# PIF_robot.net
KiCad netlist of a schematic drawn in Altium Designer
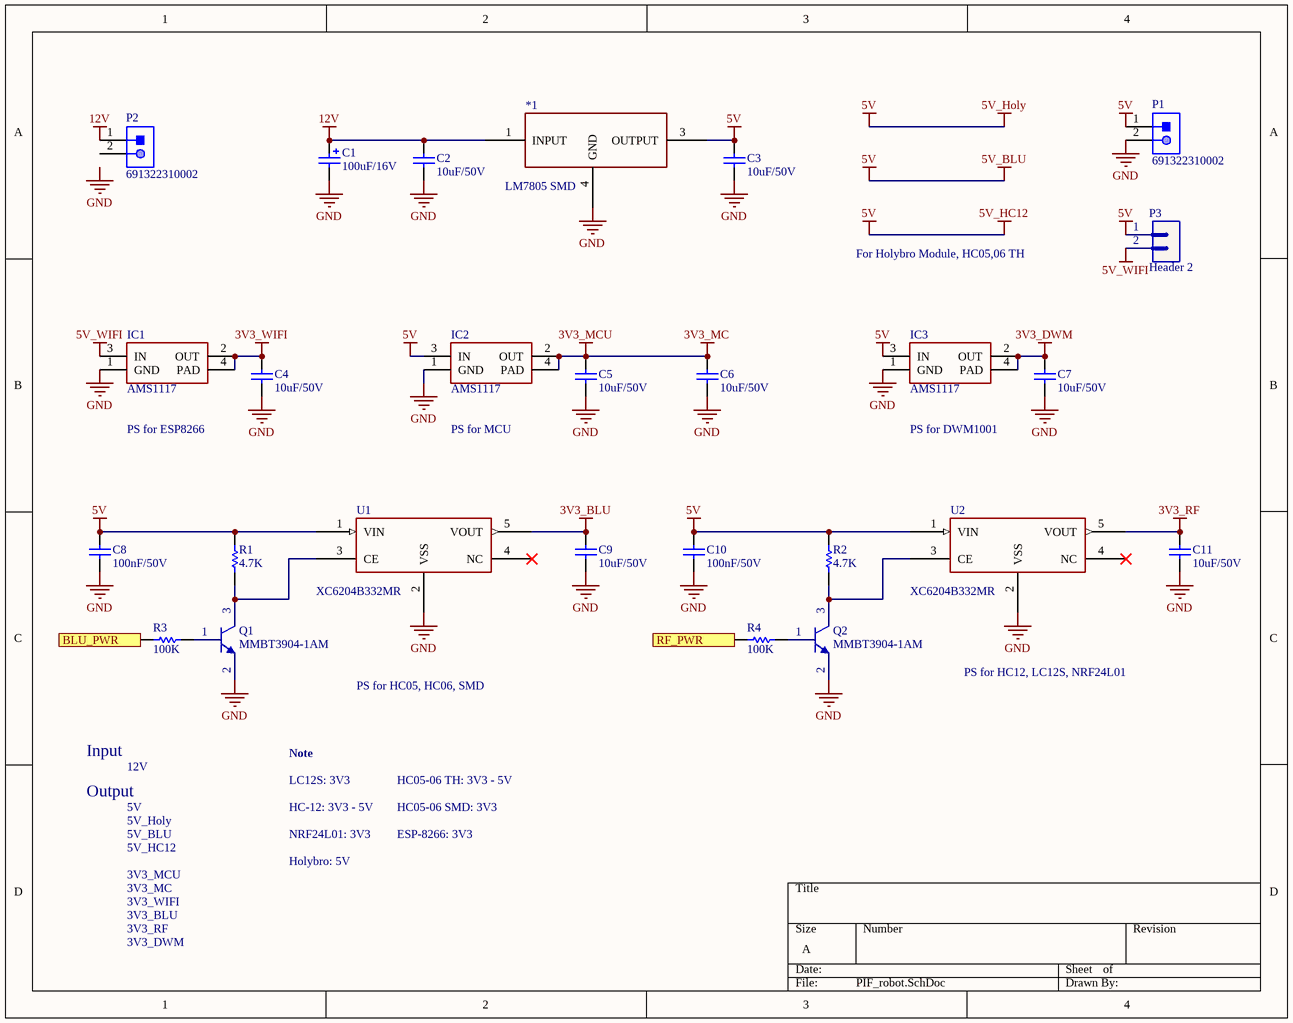
[diagram p0: PIF_robot.SchDoc]

(export (version "E")
  (design (tool "Eeschema 10.0.6"))
  (components
    (comp (ref "*1")
      (value "LM7805 SMD")
      (footprint "LM7805 SMD")
      (libsource (lib "PIF_robot") (part "LM7805 SMD"))
    )
    (comp (ref "C1")
      (value "100uF/16V")
      (footprint "CAP-SM-AL-SIZE-D-D6L6")
      (description "CAP ALUM 100UF 20% 16V SMD")
      (fields
        (field (name "MANUFACTURER") "Nichicon")
        (field (name "MANUFACTURER PART NUMBER") "UWX1C101MCL1GB")
      )
      (libsource (lib "Capacitor") (part "Cap-Al-100uF-16V-D6L5"))
    )
    (comp (ref "C2")
      (value "10uF/50V")
      (footprint "CAP-SM-0805")
      (description "CAP CER 10UF 50V X5R 0805")
      (fields
        (field (name "MANUFACTURER") "Yageo")
        (field (name "MANUFACTURER PART NUMBER") "CC0805KKX5R9BB106")
      )
      (libsource (lib "Capacitor") (part "Cap-10uF-50V-0805"))
    )
    (comp (ref "C3")
      (value "10uF/50V")
      (footprint "CAP-SM-0805")
      (description "CAP CER 10UF 50V X5R 0805")
      (fields
        (field (name "MANUFACTURER") "Yageo")
        (field (name "MANUFACTURER PART NUMBER") "CC0805KKX5R9BB106")
      )
      (libsource (lib "Capacitor") (part "Cap-10uF-50V-0805"))
    )
    (comp (ref "C4")
      (value "10uF/50V")
      (footprint "CAP-SM-0805")
      (description "CAP CER 10UF 50V X5R 0805")
      (fields
        (field (name "MANUFACTURER") "Yageo")
        (field (name "MANUFACTURER PART NUMBER") "CC0805KKX5R9BB106")
      )
      (libsource (lib "Capacitor") (part "Cap-10uF-50V-0805"))
    )
    (comp (ref "C5")
      (value "10uF/50V")
      (footprint "CAP-SM-0805")
      (description "CAP CER 10UF 50V X5R 0805")
      (fields
        (field (name "MANUFACTURER") "Yageo")
        (field (name "MANUFACTURER PART NUMBER") "CC0805KKX5R9BB106")
      )
      (libsource (lib "Capacitor") (part "Cap-10uF-50V-0805"))
    )
    (comp (ref "C6")
      (value "10uF/50V")
      (footprint "CAP-SM-0805")
      (description "CAP CER 10UF 50V X5R 0805")
      (fields
        (field (name "MANUFACTURER") "Yageo")
        (field (name "MANUFACTURER PART NUMBER") "CC0805KKX5R9BB106")
      )
      (libsource (lib "Capacitor") (part "Cap-10uF-50V-0805"))
    )
    (comp (ref "C7")
      (value "10uF/50V")
      (footprint "CAP-SM-0805")
      (description "CAP CER 10UF 50V X5R 0805")
      (fields
        (field (name "MANUFACTURER") "Yageo")
        (field (name "MANUFACTURER PART NUMBER") "CC0805KKX5R9BB106")
      )
      (libsource (lib "Capacitor") (part "Cap-10uF-50V-0805"))
    )
    (comp (ref "C8")
      (value "100nF/50V")
      (footprint "CAP-SM-0805")
      (description "CAP CER 0.1UF 50V Y5V 0805")
      (fields
        (field (name "MANUFACTURER") "Samsung Electro-Mechanics")
        (field (name "MANUFACTURER PART NUMBER") "CL21F104ZBCNNNC")
      )
      (libsource (lib "Capacitor") (part "Cap-100nF-50V-0805"))
    )
    (comp (ref "C9")
      (value "10uF/50V")
      (footprint "CAP-SM-0805")
      (description "CAP CER 10UF 50V X5R 0805")
      (fields
        (field (name "MANUFACTURER") "Yageo")
        (field (name "MANUFACTURER PART NUMBER") "CC0805KKX5R9BB106")
      )
      (libsource (lib "Capacitor") (part "Cap-10uF-50V-0805"))
    )
    (comp (ref "C10")
      (value "100nF/50V")
      (footprint "CAP-SM-0805")
      (description "CAP CER 0.1UF 50V Y5V 0805")
      (fields
        (field (name "MANUFACTURER") "Samsung Electro-Mechanics")
        (field (name "MANUFACTURER PART NUMBER") "CL21F104ZBCNNNC")
      )
      (libsource (lib "Capacitor") (part "Cap-100nF-50V-0805"))
    )
    (comp (ref "C11")
      (value "10uF/50V")
      (footprint "CAP-SM-0805")
      (description "CAP CER 10UF 50V X5R 0805")
      (fields
        (field (name "MANUFACTURER") "Yageo")
        (field (name "MANUFACTURER PART NUMBER") "CC0805KKX5R9BB106")
      )
      (libsource (lib "Capacitor") (part "Cap-10uF-50V-0805"))
    )
    (comp (ref "IC1")
      (value "AMS1117")
      (footprint "SOT223")
      (description "Available in 1.8V, 2.5V, 2.85V, 3.3V, 5V, and  Adjustable Versions")
      (libsource (lib "PI") (part "AMS1117"))
    )
    (comp (ref "IC2")
      (value "AMS1117")
      (footprint "SOT223")
      (description "Available in 1.8V, 2.5V, 2.85V, 3.3V, 5V, and  Adjustable Versions")
      (libsource (lib "PI") (part "AMS1117"))
    )
    (comp (ref "IC3")
      (value "AMS1117")
      (footprint "SOT223")
      (description "Available in 1.8V, 2.5V, 2.85V, 3.3V, 5V, and  Adjustable Versions")
      (libsource (lib "PI") (part "AMS1117"))
    )
    (comp (ref "P1")
      (value "691322310002")
      (footprint "691322310002")
      (description "WR-TBL Serie 322 Horizontal PCB Header, Pluggable, pitch 3.81mm, 2p")
      (fields (field (name "PUBLISHER") "Wurth Elektronik"))
      (libsource (lib "691322310002_Altium_WR-TBL_rev19a") (part "691322310002"))
    )
    (comp (ref "P2")
      (value "691322310002")
      (footprint "691322310002")
      (description "WR-TBL Serie 322 Horizontal PCB Header, Pluggable, pitch 3.81mm, 2p")
      (fields (field (name "PUBLISHER") "Wurth Elektronik"))
      (libsource (lib "691322310002_Altium_WR-TBL_rev19a") (part "691322310002"))
    )
    (comp (ref "P3")
      (value "Header 2")
      (footprint "JP2")
      (description "Header, 2-Pin")
      (fields (field (name "PUBLISHER") "Altium Limited"))
      (libsource (lib "PIF_C16_lib") (part "Header 2"))
    )
    (comp (ref "Q1")
      (value "MMBT3904-1AM")
      (footprint "SOT23_NEX")
      (libsource (lib "BJT") (part "MMBT3904-1AM"))
    )
    (comp (ref "Q2")
      (value "MMBT3904-1AM")
      (footprint "SOT23_NEX")
      (libsource (lib "BJT") (part "MMBT3904-1AM"))
    )
    (comp (ref "R1")
      (value "4.7K")
      (footprint "Resistor:RES-SM-0805")
      (description "RES SMD 4.7K OHM 5% 1/8W 0805")
      (fields
        (field (name "MANUFACTURER") "Yageo")
        (field (name "MANUFACTURER PART NUMBER") "RC0805JR-074K7L")
      )
      (libsource (lib "Resistor") (part "Res-4.7K-0805"))
    )
    (comp (ref "R2")
      (value "4.7K")
      (footprint "Resistor:RES-SM-0805")
      (description "RES SMD 4.7K OHM 5% 1/8W 0805")
      (fields
        (field (name "MANUFACTURER") "Yageo")
        (field (name "MANUFACTURER PART NUMBER") "RC0805JR-074K7L")
      )
      (libsource (lib "Resistor") (part "Res-4.7K-0805"))
    )
    (comp (ref "R3")
      (value "100K")
      (footprint "Resistor:RES-SM-0805")
      (description "RES 0 OHM JUMPER 0805")
      (fields
        (field (name "MANUFACTURER") "Vishay Dale")
        (field (name "MANUFACTURER PART NUMBER") "WSL080500000ZEA9")
      )
      (libsource (lib "Resistor") (part "Res-100K-0805"))
    )
    (comp (ref "R4")
      (value "100K")
      (footprint "Resistor:RES-SM-0805")
      (description "RES 0 OHM JUMPER 0805")
      (fields
        (field (name "MANUFACTURER") "Vishay Dale")
        (field (name "MANUFACTURER PART NUMBER") "WSL080500000ZEA9")
      )
      (libsource (lib "Resistor") (part "Res-100K-0805"))
    )
    (comp (ref "U1")
      (value "XC6204B332MR")
      (footprint "XC6204/05_SOT-00")
      (fields (field (name "COPYRIGHT") "Copyright (C) 2018 Accelerated Designs. All rights reserved"))
      (libsource (lib "PI") (part "XC6204B332MR"))
    )
    (comp (ref "U2")
      (value "XC6204B332MR")
      (footprint "XC6204/05_SOT-00")
      (fields (field (name "COPYRIGHT") "Copyright (C) 2018 Accelerated Designs. All rights reserved"))
      (libsource (lib "PI") (part "XC6204B332MR"))
    )
  )
  (nets
    (net (code "1") (name "/BLU_PWR") (class "Default")
      (node (ref "R3") (pin "1") (pinfunction "1_1") (pintype "passive"))
    )
    (net (code "2") (name "/RF_PWR") (class "Default")
      (node (ref "R4") (pin "1") (pinfunction "1_1") (pintype "passive"))
    )
    (net (code "3") (name "3V3_BLU") (class "Default")
      (node (ref "C9") (pin "2") (pinfunction "2_2") (pintype "passive"))
      (node (ref "U1") (pin "5") (pinfunction "VOUT_5") (pintype "output"))
    )
    (net (code "4") (name "3V3_DWM") (class "Default")
      (node (ref "C7") (pin "2") (pinfunction "2_2") (pintype "passive"))
      (node (ref "IC3") (pin "2") (pinfunction "OUT_2") (pintype "passive"))
      (node (ref "IC3") (pin "4") (pinfunction "PAD_4") (pintype "passive"))
    )
    (net (code "5") (name "3V3_MC") (class "Default")
      (node (ref "C5") (pin "2") (pinfunction "2_2") (pintype "passive"))
      (node (ref "C6") (pin "2") (pinfunction "2_2") (pintype "passive"))
      (node (ref "IC2") (pin "2") (pinfunction "OUT_2") (pintype "passive"))
      (node (ref "IC2") (pin "4") (pinfunction "PAD_4") (pintype "passive"))
    )
    (net (code "6") (name "3V3_RF") (class "Default")
      (node (ref "C11") (pin "2") (pinfunction "2_2") (pintype "passive"))
      (node (ref "U2") (pin "5") (pinfunction "VOUT_5") (pintype "output"))
    )
    (net (code "7") (name "3V3_WIFI") (class "Default")
      (node (ref "C4") (pin "2") (pinfunction "2_2") (pintype "passive"))
      (node (ref "IC1") (pin "2") (pinfunction "OUT_2") (pintype "passive"))
      (node (ref "IC1") (pin "4") (pinfunction "PAD_4") (pintype "passive"))
    )
    (net (code "8") (name "5V") (class "Default")
      (node (ref "*1") (pin "3") (pinfunction "OUTPUT_3") (pintype "passive"))
      (node (ref "C10") (pin "2") (pinfunction "2_2") (pintype "passive"))
      (node (ref "C3") (pin "2") (pinfunction "2_2") (pintype "passive"))
      (node (ref "C8") (pin "2") (pinfunction "2_2") (pintype "passive"))
      (node (ref "IC2") (pin "3") (pinfunction "IN_3") (pintype "passive"))
      (node (ref "IC3") (pin "3") (pinfunction "IN_3") (pintype "passive"))
      (node (ref "P1") (pin "1") (pinfunction "1_1") (pintype "passive"))
      (node (ref "P3") (pin "1") (pinfunction "1_1") (pintype "passive"))
      (node (ref "R1") (pin "2") (pinfunction "2_2") (pintype "passive"))
      (node (ref "R2") (pin "2") (pinfunction "2_2") (pintype "passive"))
      (node (ref "U1") (pin "1") (pinfunction "VIN_1") (pintype "input"))
      (node (ref "U2") (pin "1") (pinfunction "VIN_1") (pintype "input"))
    )
    (net (code "9") (name "5V_WIFI") (class "Default")
      (node (ref "IC1") (pin "3") (pinfunction "IN_3") (pintype "passive"))
      (node (ref "P3") (pin "2") (pinfunction "2_2") (pintype "passive"))
    )
    (net (code "10") (name "12V") (class "Default")
      (node (ref "*1") (pin "1") (pinfunction "INPUT_1") (pintype "passive"))
      (node (ref "C1") (pin "1") (pinfunction "1_1") (pintype "passive"))
      (node (ref "C2") (pin "1") (pinfunction "1_1") (pintype "passive"))
      (node (ref "P2") (pin "1") (pinfunction "1_1") (pintype "passive"))
    )
    (net (code "11") (name "GND") (class "Default")
      (node (ref "*1") (pin "4") (pinfunction "GND_4") (pintype "passive"))
      (node (ref "C1") (pin "2") (pinfunction "2_2") (pintype "passive"))
      (node (ref "C10") (pin "1") (pinfunction "1_1") (pintype "passive"))
      (node (ref "C11") (pin "1") (pinfunction "1_1") (pintype "passive"))
      (node (ref "C2") (pin "2") (pinfunction "2_2") (pintype "passive"))
      (node (ref "C3") (pin "1") (pinfunction "1_1") (pintype "passive"))
      (node (ref "C4") (pin "1") (pinfunction "1_1") (pintype "passive"))
      (node (ref "C5") (pin "1") (pinfunction "1_1") (pintype "passive"))
      (node (ref "C6") (pin "1") (pinfunction "1_1") (pintype "passive"))
      (node (ref "C7") (pin "1") (pinfunction "1_1") (pintype "passive"))
      (node (ref "C8") (pin "1") (pinfunction "1_1") (pintype "passive"))
      (node (ref "C9") (pin "1") (pinfunction "1_1") (pintype "passive"))
      (node (ref "IC1") (pin "1") (pinfunction "GND_1") (pintype "passive"))
      (node (ref "IC2") (pin "1") (pinfunction "GND_1") (pintype "passive"))
      (node (ref "IC3") (pin "1") (pinfunction "GND_1") (pintype "passive"))
      (node (ref "P1") (pin "2") (pinfunction "2_2") (pintype "passive"))
      (node (ref "Q1") (pin "2") (pinfunction "E_2") (pintype "passive"))
      (node (ref "Q2") (pin "2") (pinfunction "E_2") (pintype "passive"))
      (node (ref "U1") (pin "2") (pinfunction "VSS_2") (pintype "passive"))
      (node (ref "U2") (pin "2") (pinfunction "VSS_2") (pintype "passive"))
    )
    (net (code "12") (name "Net-(Q1-B)") (class "Default")
      (node (ref "Q1") (pin "1") (pinfunction "B_1") (pintype "passive"))
      (node (ref "R3") (pin "2") (pinfunction "2_2") (pintype "passive"))
    )
    (net (code "13") (name "Net-(Q1-C)") (class "Default")
      (node (ref "Q1") (pin "3") (pinfunction "C_3") (pintype "passive"))
      (node (ref "R1") (pin "1") (pinfunction "1_1") (pintype "passive"))
      (node (ref "U1") (pin "3") (pinfunction "CE_3") (pintype "passive"))
    )
    (net (code "14") (name "Net-(Q2-B)") (class "Default")
      (node (ref "Q2") (pin "1") (pinfunction "B_1") (pintype "passive"))
      (node (ref "R4") (pin "2") (pinfunction "2_2") (pintype "passive"))
    )
    (net (code "15") (name "Net-(Q2-C)") (class "Default")
      (node (ref "Q2") (pin "3") (pinfunction "C_3") (pintype "passive"))
      (node (ref "R2") (pin "1") (pinfunction "1_1") (pintype "passive"))
      (node (ref "U2") (pin "3") (pinfunction "CE_3") (pintype "passive"))
    )
    (net (code "16") (name "unconnected-(P2-Pad2)") (class "Default")
      (node (ref "P2") (pin "2") (pinfunction "2_2") (pintype "passive"))
    )
    (net (code "17") (name "unconnected-(U1-NC-Pad4)") (class "Default")
      (node (ref "U1") (pin "4") (pinfunction "NC_4") (pintype "passive+no_connect"))
    )
    (net (code "18") (name "unconnected-(U2-NC-Pad4)") (class "Default")
      (node (ref "U2") (pin "4") (pinfunction "NC_4") (pintype "passive+no_connect"))
    )
  )
)
